# Breakout_UVB.net
KiCad netlist of a schematic drawn in EAGLE
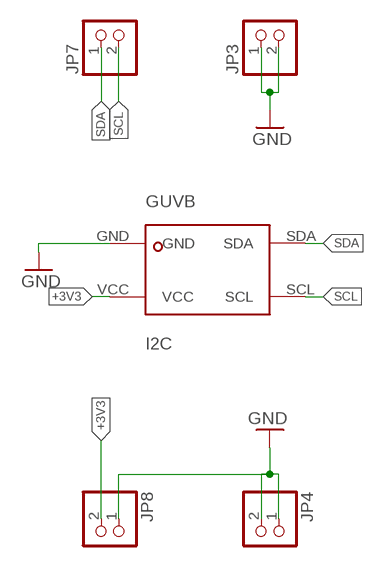
[diagram p0: schematic, sheet 1]

(export (version "E")
  (design (tool "Eeschema 10.0.6"))
  (components
    (comp (ref "GUVB")
      (value "I2C")
      (footprint "eagle-import:GUV_A_B")
      (libsource (lib "eagle-import") (part "GUVB-C31SM"))
    )
    (comp (ref "JP3")
      (value "PINHD-1X2")
      (footprint "eagle-import:1X02(PAD_REDUZIDO)")
      (libsource (lib "eagle-import") (part "PINHD-1X2"))
    )
    (comp (ref "JP4")
      (value "PINHD-1X2")
      (footprint "eagle-import:1X02(PAD_REDUZIDO)")
      (libsource (lib "eagle-import") (part "PINHD-1X2"))
    )
    (comp (ref "JP7")
      (value "PINHD-1X2")
      (footprint "eagle-import:1X02(PAD_REDUZIDO)")
      (libsource (lib "eagle-import") (part "PINHD-1X2"))
    )
    (comp (ref "JP8")
      (value "PINHD-1X2")
      (footprint "eagle-import:1X02(PAD_REDUZIDO)")
      (libsource (lib "eagle-import") (part "PINHD-1X2"))
    )
  )
  (nets
    (net (code "1") (name "+3V3") (class "Default")
      (node (ref "GUVB") (pin "VCC") (pinfunction "VCC_VCC") (pintype "bidirectional"))
      (node (ref "JP8") (pin "2") (pinfunction "2_2") (pintype "passive"))
    )
    (net (code "2") (name "GND") (class "Default")
      (node (ref "GUVB") (pin "GND") (pinfunction "GND_GND") (pintype "bidirectional"))
      (node (ref "JP3") (pin "1") (pinfunction "1_1") (pintype "passive"))
      (node (ref "JP3") (pin "2") (pinfunction "2_2") (pintype "passive"))
      (node (ref "JP4") (pin "1") (pinfunction "1_1") (pintype "passive"))
      (node (ref "JP4") (pin "2") (pinfunction "2_2") (pintype "passive"))
      (node (ref "JP8") (pin "1") (pinfunction "1_1") (pintype "passive"))
    )
    (net (code "3") (name "SCL") (class "Default")
      (node (ref "GUVB") (pin "SCL") (pinfunction "SCL_SCL") (pintype "bidirectional"))
      (node (ref "JP7") (pin "2") (pinfunction "2_2") (pintype "passive"))
    )
    (net (code "4") (name "SDA") (class "Default")
      (node (ref "GUVB") (pin "SDA") (pinfunction "SDA_SDA") (pintype "bidirectional"))
      (node (ref "JP7") (pin "1") (pinfunction "1_1") (pintype "passive"))
    )
  )
)
